# AP5100.net
KiCad netlist of a schematic drawn in EAGLE
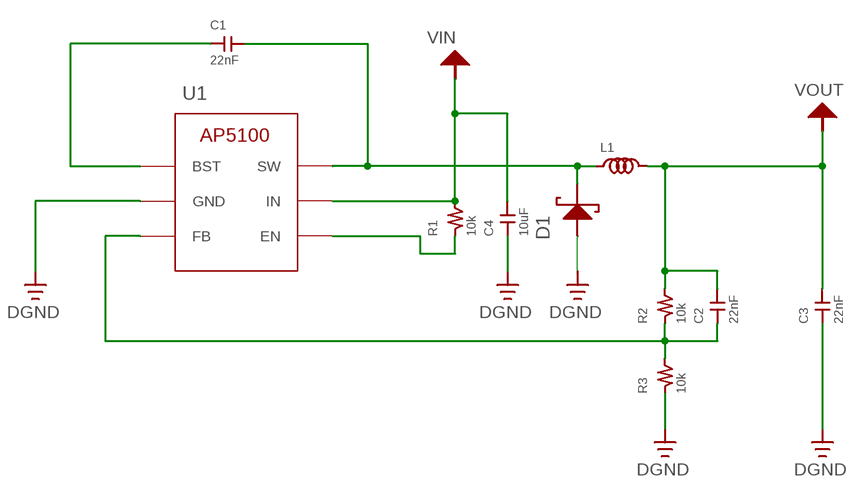
[diagram p0: schematic, sheet 1]

(export (version "E")
  (design (tool "Eeschema 10.0.6"))
  (components
    (comp (ref "C1")
      (value "22nF")
      (footprint "eagle-import:2012")
      (libsource (lib "eagle-import") (part "CAPACITOR_CHIP2012"))
    )
    (comp (ref "C2")
      (value "22nF")
      (footprint "eagle-import:2012")
      (libsource (lib "eagle-import") (part "CAPACITOR_CHIP2012"))
    )
    (comp (ref "C3")
      (value "22nF")
      (footprint "eagle-import:2012")
      (libsource (lib "eagle-import") (part "CAPACITOR_CHIP2012"))
    )
    (comp (ref "C4")
      (value "10uF")
      (footprint "eagle-import:2012")
      (libsource (lib "eagle-import") (part "CAPACITOR_CHIP2012"))
    )
    (comp (ref "D1")
      (value "BAT60JFILM")
      (footprint "eagle-import:SOD323")
      (libsource (lib "eagle-import") (part "BAT60JFILM"))
    )
    (comp (ref "L1")
      (value "INDUCTOR2012")
      (footprint "eagle-import:2012")
      (libsource (lib "eagle-import") (part "INDUCTOR2012"))
    )
    (comp (ref "R1")
      (value "10k")
      (footprint "eagle-import:2012")
      (libsource (lib "eagle-import") (part "RESISTOR_CHIP_2012"))
    )
    (comp (ref "R2")
      (value "10k")
      (footprint "eagle-import:2012")
      (libsource (lib "eagle-import") (part "RESISTOR_CHIP_2012"))
    )
    (comp (ref "R3")
      (value "10k")
      (footprint "eagle-import:2012")
      (libsource (lib "eagle-import") (part "RESISTOR_CHIP_2012"))
    )
    (comp (ref "U1")
      (value "AP5100")
      (footprint "eagle-import:SOT-26")
      (libsource (lib "eagle-import") (part "AP5100"))
    )
  )
  (nets
    (net (code "1") (name "DGND") (class "Default")
      (node (ref "C3") (pin "P$1") (pinfunction "P$1_P$1") (pintype "passive"))
      (node (ref "C4") (pin "P$1") (pinfunction "P$1_P$1") (pintype "passive"))
      (node (ref "D1") (pin "A") (pinfunction "A_A") (pintype "passive"))
      (node (ref "R3") (pin "P$1") (pinfunction "P$1_P$1") (pintype "passive"))
      (node (ref "U1") (pin "P2") (pinfunction "GND_P2") (pintype "power_in"))
    )
    (net (code "2") (name "Net-(U1-BST)") (class "Default")
      (node (ref "C1") (pin "P$1") (pinfunction "P$1_P$1") (pintype "passive"))
      (node (ref "U1") (pin "P1") (pinfunction "BST_P1") (pintype "bidirectional"))
    )
    (net (code "3") (name "Net-(U1-EN)") (class "Default")
      (node (ref "R1") (pin "P$1") (pinfunction "P$1_P$1") (pintype "passive"))
      (node (ref "U1") (pin "P4") (pinfunction "EN_P4") (pintype "bidirectional"))
    )
    (net (code "4") (name "Net-(U1-FB)") (class "Default")
      (node (ref "C2") (pin "P$1") (pinfunction "P$1_P$1") (pintype "passive"))
      (node (ref "R2") (pin "P$1") (pinfunction "P$1_P$1") (pintype "passive"))
      (node (ref "R3") (pin "P$2") (pinfunction "P$2_P$2") (pintype "passive"))
      (node (ref "U1") (pin "P3") (pinfunction "FB_P3") (pintype "bidirectional"))
    )
    (net (code "5") (name "Net-(U1-SW)") (class "Default")
      (node (ref "C1") (pin "P$2") (pinfunction "P$2_P$2") (pintype "passive"))
      (node (ref "D1") (pin "K") (pinfunction "K_K") (pintype "passive"))
      (node (ref "L1") (pin "P$1") (pinfunction "P$1_P$1") (pintype "passive"))
      (node (ref "U1") (pin "P6") (pinfunction "SW_P6") (pintype "bidirectional"))
    )
    (net (code "6") (name "VIN") (class "Default")
      (node (ref "C4") (pin "P$2") (pinfunction "P$2_P$2") (pintype "passive"))
      (node (ref "R1") (pin "P$2") (pinfunction "P$2_P$2") (pintype "passive"))
      (node (ref "U1") (pin "P5") (pinfunction "IN_P5") (pintype "bidirectional"))
    )
    (net (code "7") (name "VOUT") (class "Default")
      (node (ref "C2") (pin "P$2") (pinfunction "P$2_P$2") (pintype "passive"))
      (node (ref "C3") (pin "P$2") (pinfunction "P$2_P$2") (pintype "passive"))
      (node (ref "L1") (pin "P$2") (pinfunction "P$2_P$2") (pintype "passive"))
      (node (ref "R2") (pin "P$2") (pinfunction "P$2_P$2") (pintype "passive"))
    )
  )
)
